# CurrentSensingConverter.net
KiCad netlist of a schematic drawn in EAGLE
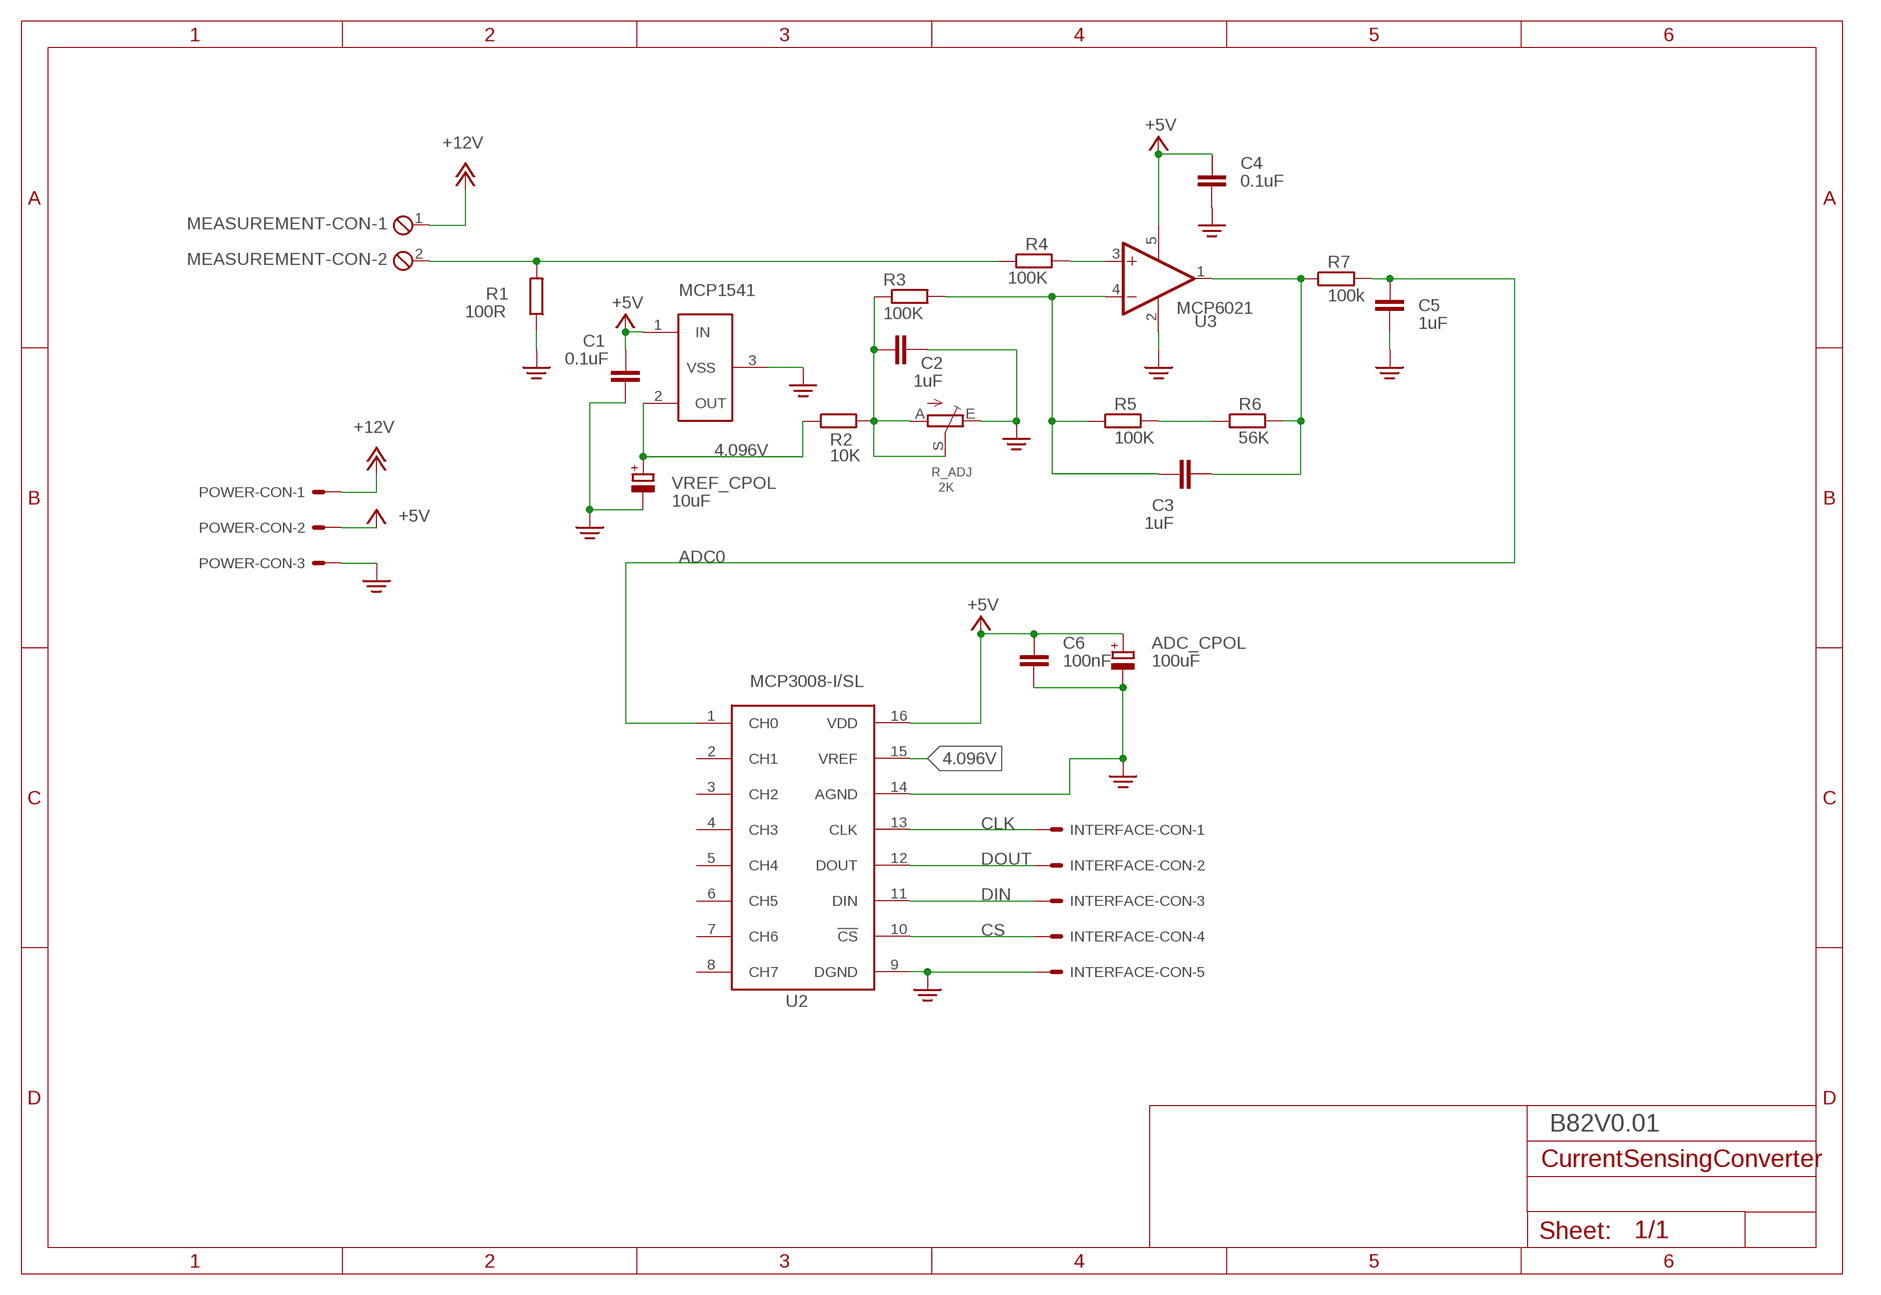
[diagram p0: schematic, sheet 1]

(export (version "E")
  (design (tool "Eeschema 10.0.6"))
  (components
    (comp (ref "ADC_CPOL")
      (value "100uF")
      (footprint "eagle-import:D_7343-31R")
      (libsource (lib "eagle-import") (part "CPOL-EUD/7343-31R"))
    )
    (comp (ref "C1")
      (value "0.1uF")
      (footprint "eagle-import:C1206")
      (libsource (lib "eagle-import") (part "C-EUC1206"))
    )
    (comp (ref "C2")
      (value "1uF")
      (footprint "eagle-import:C1206")
      (libsource (lib "eagle-import") (part "C-EUC1206"))
    )
    (comp (ref "C3")
      (value "1uF")
      (footprint "eagle-import:C1206")
      (libsource (lib "eagle-import") (part "C-EUC1206"))
    )
    (comp (ref "C4")
      (value "0.1uF")
      (footprint "eagle-import:C1206")
      (libsource (lib "eagle-import") (part "C-EUC1206"))
    )
    (comp (ref "C5")
      (value "1uF")
      (footprint "eagle-import:C1206")
      (libsource (lib "eagle-import") (part "C-EUC1206"))
    )
    (comp (ref "C6")
      (value "100nF")
      (footprint "eagle-import:C1206")
      (libsource (lib "eagle-import") (part "C-EUC1206"))
    )
    (comp (ref "INTERFACE-CON")
      (value "22-05-7058-05")
      (footprint "eagle-import:7395-05")
      (libsource (lib "eagle-import") (part "22-?-0505-7058"))
    )
    (comp (ref "MEASUREMENT-CON")
      (value "MPT2")
      (footprint "eagle-import:2POL254")
      (libsource (lib "eagle-import") (part "MPT2"))
    )
    (comp (ref "POWER-CON")
      (value "22-05-7038-03")
      (footprint "eagle-import:7395-03")
      (libsource (lib "eagle-import") (part "22-?-0305-7038"))
    )
    (comp (ref "R1")
      (value "100R")
      (footprint "eagle-import:R1206")
      (libsource (lib "eagle-import") (part "R-EU_R1206"))
    )
    (comp (ref "R2")
      (value "10K")
      (footprint "eagle-import:R1206")
      (libsource (lib "eagle-import") (part "R-EU_R1206"))
    )
    (comp (ref "R3")
      (value "100K")
      (footprint "eagle-import:R1206")
      (libsource (lib "eagle-import") (part "R-EU_R1206"))
    )
    (comp (ref "R4")
      (value "100K")
      (footprint "eagle-import:R1206")
      (libsource (lib "eagle-import") (part "R-EU_R1206"))
    )
    (comp (ref "R5")
      (value "100K")
      (footprint "eagle-import:R1206")
      (libsource (lib "eagle-import") (part "R-EU_R1206"))
    )
    (comp (ref "R6")
      (value "56K")
      (footprint "eagle-import:R1206")
      (libsource (lib "eagle-import") (part "R-EU_R1206"))
    )
    (comp (ref "R7")
      (value "100k")
      (footprint "eagle-import:R1206")
      (libsource (lib "eagle-import") (part "R-EU_R1206"))
    )
    (comp (ref "R_ADJ")
      (value "2K")
      (footprint "eagle-import:B25P")
      (libsource (lib "eagle-import") (part "TRIM_EU-B25P"))
    )
    (comp (ref "U1")
      (value "U1")
      (footprint "eagle-import:SOT23")
      (libsource (lib "eagle-import") (part "MCP1541T-I/TT"))
    )
    (comp (ref "U2")
      (value "MCP3008-I/SL")
      (footprint "eagle-import:SO16")
      (libsource (lib "eagle-import") (part "MCP3008-I/SL"))
    )
    (comp (ref "U3")
      (value "MCP6021")
      (footprint "eagle-import:SOT23-5L")
      (libsource (lib "eagle-import") (part "MCP6021-SOT23"))
    )
    (comp (ref "VREF_CPOL")
      (value "10uF")
      (footprint "eagle-import:D_7343-31R")
      (libsource (lib "eagle-import") (part "CPOL-EUD/7343-31R"))
    )
  )
  (nets
    (net (code "1") (name "+5V") (class "Default")
      (node (ref "ADC_CPOL") (pin "+") (pinfunction "+_+") (pintype "passive"))
      (node (ref "C1") (pin "1") (pinfunction "1_1") (pintype "passive"))
      (node (ref "C4") (pin "1") (pinfunction "1_1") (pintype "passive"))
      (node (ref "C6") (pin "1") (pinfunction "1_1") (pintype "passive"))
      (node (ref "POWER-CON") (pin "2") (pinfunction "S_2") (pintype "passive"))
      (node (ref "U1") (pin "1") (pinfunction "IN_1") (pintype "bidirectional"))
      (node (ref "U2") (pin "16") (pinfunction "VDD_16") (pintype "power_in"))
      (node (ref "U3") (pin "5") (pinfunction "V+_5") (pintype "power_in"))
    )
    (net (code "2") (name "+12V") (class "Default")
      (node (ref "MEASUREMENT-CON") (pin "1") (pinfunction "1_1") (pintype "passive"))
      (node (ref "POWER-CON") (pin "1") (pinfunction "S_1") (pintype "passive"))
    )
    (net (code "3") (name "/ADC0") (class "Default")
      (node (ref "C5") (pin "1") (pinfunction "1_1") (pintype "passive"))
      (node (ref "R7") (pin "2") (pinfunction "2_2") (pintype "passive"))
      (node (ref "U2") (pin "1") (pinfunction "CH0_1") (pintype "bidirectional"))
    )
    (net (code "4") (name "/CLK") (class "Default")
      (node (ref "INTERFACE-CON") (pin "1") (pinfunction "S_1") (pintype "passive"))
      (node (ref "U2") (pin "13") (pinfunction "CLK_13") (pintype "input"))
    )
    (net (code "5") (name "/CS") (class "Default")
      (node (ref "INTERFACE-CON") (pin "4") (pinfunction "S_4") (pintype "passive"))
      (node (ref "U2") (pin "10") (pinfunction "~{CS}_10") (pintype "input"))
    )
    (net (code "6") (name "/DIN") (class "Default")
      (node (ref "INTERFACE-CON") (pin "3") (pinfunction "S_3") (pintype "passive"))
      (node (ref "U2") (pin "11") (pinfunction "DIN_11") (pintype "input"))
    )
    (net (code "7") (name "/DOUT") (class "Default")
      (node (ref "INTERFACE-CON") (pin "2") (pinfunction "S_2") (pintype "passive"))
      (node (ref "U2") (pin "12") (pinfunction "DOUT_12") (pintype "output"))
    )
    (net (code "8") (name "4.096V") (class "Default")
      (node (ref "R2") (pin "1") (pinfunction "1_1") (pintype "passive"))
      (node (ref "U1") (pin "2") (pinfunction "OUT_2") (pintype "bidirectional"))
      (node (ref "U2") (pin "15") (pinfunction "VREF_15") (pintype "bidirectional"))
      (node (ref "VREF_CPOL") (pin "+") (pinfunction "+_+") (pintype "passive"))
    )
    (net (code "9") (name "Net-(C2-Pad1)") (class "Default")
      (node (ref "C2") (pin "1") (pinfunction "1_1") (pintype "passive"))
      (node (ref "R2") (pin "2") (pinfunction "2_2") (pintype "passive"))
      (node (ref "R3") (pin "1") (pinfunction "1_1") (pintype "passive"))
      (node (ref "R_ADJ") (pin "A") (pinfunction "A_A") (pintype "passive"))
      (node (ref "R_ADJ") (pin "S") (pinfunction "S_S") (pintype "passive"))
    )
    (net (code "10") (name "Net-(MEASUREMENT-CONB-1)") (class "Default")
      (node (ref "MEASUREMENT-CON") (pin "2") (pinfunction "1_2") (pintype "passive"))
      (node (ref "R1") (pin "2") (pinfunction "2_2") (pintype "passive"))
      (node (ref "R4") (pin "1") (pinfunction "1_1") (pintype "passive"))
    )
    (net (code "11") (name "Net-(R5-Pad2)") (class "Default")
      (node (ref "R5") (pin "2") (pinfunction "2_2") (pintype "passive"))
      (node (ref "R6") (pin "1") (pinfunction "1_1") (pintype "passive"))
    )
    (net (code "12") (name "Net-(U3-+IN)") (class "Default")
      (node (ref "R4") (pin "2") (pinfunction "2_2") (pintype "passive"))
      (node (ref "U3") (pin "3") (pinfunction "+IN_3") (pintype "input"))
    )
    (net (code "13") (name "Net-(U3--IN)") (class "Default")
      (node (ref "C3") (pin "1") (pinfunction "1_1") (pintype "passive"))
      (node (ref "R3") (pin "2") (pinfunction "2_2") (pintype "passive"))
      (node (ref "R5") (pin "1") (pinfunction "1_1") (pintype "passive"))
      (node (ref "U3") (pin "4") (pinfunction "-IN_4") (pintype "input"))
    )
    (net (code "14") (name "Net-(U3-OUT)") (class "Default")
      (node (ref "C3") (pin "2") (pinfunction "2_2") (pintype "passive"))
      (node (ref "R6") (pin "2") (pinfunction "2_2") (pintype "passive"))
      (node (ref "R7") (pin "1") (pinfunction "1_1") (pintype "passive"))
      (node (ref "U3") (pin "1") (pinfunction "OUT_1") (pintype "output"))
    )
    (net (code "15") (name "PE") (class "Default")
      (node (ref "ADC_CPOL") (pin "-") (pinfunction "-_-") (pintype "passive"))
      (node (ref "C1") (pin "2") (pinfunction "2_2") (pintype "passive"))
      (node (ref "C2") (pin "2") (pinfunction "2_2") (pintype "passive"))
      (node (ref "C4") (pin "2") (pinfunction "2_2") (pintype "passive"))
      (node (ref "C5") (pin "2") (pinfunction "2_2") (pintype "passive"))
      (node (ref "C6") (pin "2") (pinfunction "2_2") (pintype "passive"))
      (node (ref "INTERFACE-CON") (pin "5") (pinfunction "S_5") (pintype "passive"))
      (node (ref "POWER-CON") (pin "3") (pinfunction "S_3") (pintype "passive"))
      (node (ref "R1") (pin "1") (pinfunction "1_1") (pintype "passive"))
      (node (ref "R_ADJ") (pin "E") (pinfunction "E_E") (pintype "passive"))
      (node (ref "U1") (pin "3") (pinfunction "VSS_3") (pintype "bidirectional"))
      (node (ref "U2") (pin "14") (pinfunction "AGND_14") (pintype "power_in"))
      (node (ref "U2") (pin "9") (pinfunction "DGND_9") (pintype "power_in"))
      (node (ref "U3") (pin "2") (pinfunction "V-_2") (pintype "power_in"))
      (node (ref "VREF_CPOL") (pin "-") (pinfunction "-_-") (pintype "passive"))
    )
    (net (code "16") (name "unconnected-(U2-CH1-Pad2)") (class "Default")
      (node (ref "U2") (pin "2") (pinfunction "CH1_2") (pintype "bidirectional"))
    )
    (net (code "17") (name "unconnected-(U2-CH2-Pad3)") (class "Default")
      (node (ref "U2") (pin "3") (pinfunction "CH2_3") (pintype "bidirectional"))
    )
    (net (code "18") (name "unconnected-(U2-CH3-Pad4)") (class "Default")
      (node (ref "U2") (pin "4") (pinfunction "CH3_4") (pintype "bidirectional"))
    )
    (net (code "19") (name "unconnected-(U2-CH4-Pad5)") (class "Default")
      (node (ref "U2") (pin "5") (pinfunction "CH4_5") (pintype "bidirectional"))
    )
    (net (code "20") (name "unconnected-(U2-CH5-Pad6)") (class "Default")
      (node (ref "U2") (pin "6") (pinfunction "CH5_6") (pintype "bidirectional"))
    )
    (net (code "21") (name "unconnected-(U2-CH6-Pad7)") (class "Default")
      (node (ref "U2") (pin "7") (pinfunction "CH6_7") (pintype "bidirectional"))
    )
    (net (code "22") (name "unconnected-(U2-CH7-Pad8)") (class "Default")
      (node (ref "U2") (pin "8") (pinfunction "CH7_8") (pintype "bidirectional"))
    )
  )
)
